# BOTTOM_BRD_v_1_0_3.net
KiCad netlist of a schematic drawn in EAGLE
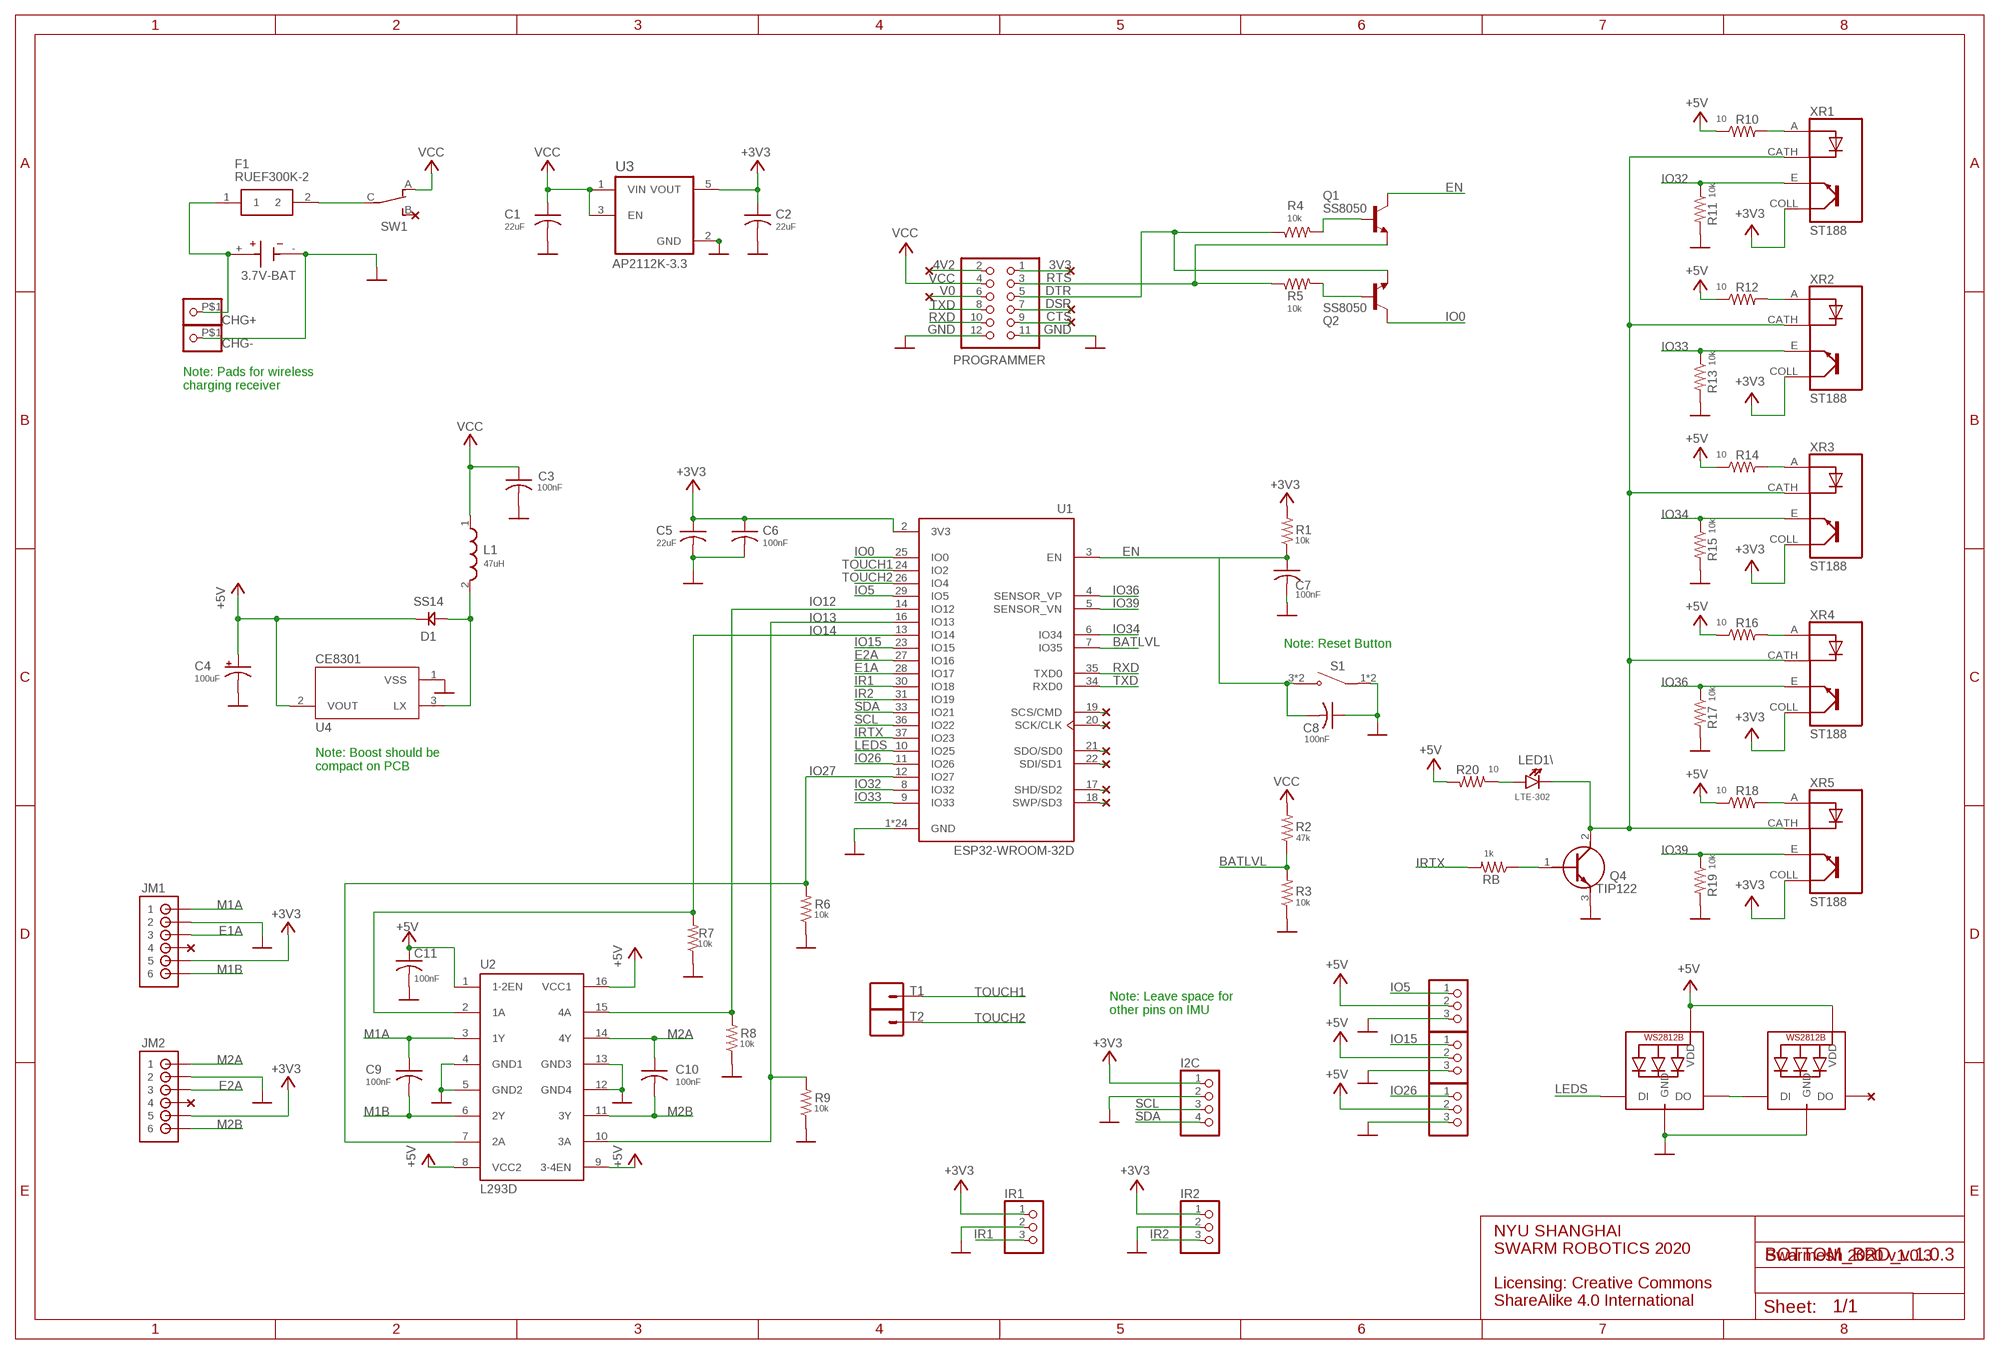
[diagram p0: schematic, sheet 1]

(export (version "E")
  (design (tool "Eeschema 10.0.6"))
  (components
    (comp (ref "BT")
      (value "3.7V-BAT")
      (footprint "eagle-import:BAT_6S-AA")
      (fields (field (name "MF") "MPD") (field (name "MP") "6S-AA"))
      (libsource (lib "eagle-import") (part "6S-AA"))
    )
    (comp (ref "C1")
      (value "22uF")
      (footprint "eagle-import:C0805")
      (libsource (lib "eagle-import") (part "C-USC0805"))
    )
    (comp (ref "C2")
      (value "22uF")
      (footprint "eagle-import:C0805")
      (libsource (lib "eagle-import") (part "C-USC0805"))
    )
    (comp (ref "C3")
      (value "100nF")
      (footprint "eagle-import:C0805")
      (libsource (lib "eagle-import") (part "C-USC0805"))
    )
    (comp (ref "C4")
      (value "100uF")
      (footprint "eagle-import:153CLV-0605")
      (libsource (lib "eagle-import") (part "CPOL-US153CLV-0605"))
    )
    (comp (ref "C5")
      (value "22uF")
      (footprint "eagle-import:C0805")
      (libsource (lib "eagle-import") (part "C-USC0805"))
    )
    (comp (ref "C6")
      (value "100nF")
      (footprint "eagle-import:C0805")
      (libsource (lib "eagle-import") (part "C-USC0805"))
    )
    (comp (ref "C7")
      (value "100nF")
      (footprint "eagle-import:C0805")
      (libsource (lib "eagle-import") (part "C-USC0805"))
    )
    (comp (ref "C8")
      (value "100nF")
      (footprint "eagle-import:C0805")
      (libsource (lib "eagle-import") (part "C-USC0805"))
    )
    (comp (ref "C9")
      (value "100nF")
      (footprint "eagle-import:C0805")
      (libsource (lib "eagle-import") (part "C-USC0805"))
    )
    (comp (ref "C10")
      (value "100nF")
      (footprint "eagle-import:C0805")
      (libsource (lib "eagle-import") (part "C-USC0805"))
    )
    (comp (ref "C11")
      (value "100nF")
      (footprint "eagle-import:C0805")
      (libsource (lib "eagle-import") (part "C-USC0805"))
    )
    (comp (ref "CHARGING")
      (value "WS2812B5050")
      (footprint "eagle-import:WS2812B")
      (libsource (lib "eagle-import") (part "WS2812B5050"))
    )
    (comp (ref "CHG+")
      (value "PINHD-1X1-BIGPOGO")
      (footprint "eagle-import:1X1-BIGPOGO")
      (libsource (lib "eagle-import") (part "PINHD-1X1-BIGPOGO"))
    )
    (comp (ref "CHG-")
      (value "PINHD-1X1-BIGPOGO")
      (footprint "eagle-import:1X1-BIGPOGO")
      (libsource (lib "eagle-import") (part "PINHD-1X1-BIGPOGO"))
    )
    (comp (ref "D1")
      (value "SS14")
      (footprint "eagle-import:DO214")
      (fields (field (name "MF") "ON Semiconductor"))
      (libsource (lib "eagle-import") (part "SS14"))
    )
    (comp (ref "F1")
      (value "RUEF300K-2")
      (footprint "eagle-import:RUEF300K2")
      (libsource (lib "eagle-import") (part "RUEF300K-2"))
    )
    (comp (ref "GPIO5")
      (value "PINHD-1X3")
      (footprint "eagle-import:1X03")
      (libsource (lib "eagle-import") (part "PINHD-1X3"))
    )
    (comp (ref "GPIO15")
      (value "PINHD-1X3")
      (footprint "eagle-import:1X03")
      (libsource (lib "eagle-import") (part "PINHD-1X3"))
    )
    (comp (ref "GPIO26")
      (value "PINHD-1X3")
      (footprint "eagle-import:1X03")
      (libsource (lib "eagle-import") (part "PINHD-1X3"))
    )
    (comp (ref "I2C")
      (value "PINHD-1X4")
      (footprint "eagle-import:1X04")
      (libsource (lib "eagle-import") (part "PINHD-1X4"))
    )
    (comp (ref "IR1")
      (value "PINHD-1X3")
      (footprint "eagle-import:1X03")
      (libsource (lib "eagle-import") (part "PINHD-1X3"))
    )
    (comp (ref "IR2")
      (value "PINHD-1X3")
      (footprint "eagle-import:1X03")
      (libsource (lib "eagle-import") (part "PINHD-1X3"))
    )
    (comp (ref "JM1")
      (value "B6B-ZR")
      (footprint "eagle-import:B6B-ZR")
      (fields (field (name "MF") "JST"))
      (libsource (lib "eagle-import") (part "B6B-ZR"))
    )
    (comp (ref "JM2")
      (value "B6B-ZR")
      (footprint "eagle-import:B6B-ZR")
      (fields (field (name "MF") "JST"))
      (libsource (lib "eagle-import") (part "B6B-ZR"))
    )
    (comp (ref "L1")
      (value "47uH")
      (footprint "eagle-import:INDP5858X480N")
      (fields (field (name "MF") "Bourns") (field (name "MP") "SDR0604-100KL"))
      (libsource (lib "eagle-import") (part "SDR0604-100KL"))
    )
    (comp (ref "LED1\\")
      (value "LTE-302")
      (footprint "eagle-import:LTE-302")
      (fields (field (name "DIGI-KEY_PART_NUMBER") "160-1930-ND") (field (name "MF") "Lite-On Inc."))
      (libsource (lib "eagle-import") (part "LTE-302"))
    )
    (comp (ref "PROGRAMMER")
      (value "PINHD-2X6")
      (footprint "eagle-import:2X06")
      (libsource (lib "eagle-import") (part "PINHD-2X6"))
    )
    (comp (ref "Q1")
      (value "SS8050")
      (footprint "eagle-import:SOT23")
      (libsource (lib "eagle-import") (part "BC850"))
    )
    (comp (ref "Q2")
      (value "SS8050")
      (footprint "eagle-import:SOT23")
      (libsource (lib "eagle-import") (part "BC850"))
    )
    (comp (ref "Q4")
      (value "TIP122")
      (footprint "eagle-import:TO270P460X1020X2008-3P")
      (fields (field (name "MOUSER_PART_NUMBER") "511-TIP122"))
      (libsource (lib "eagle-import") (part "TIP122"))
    )
    (comp (ref "R1")
      (value "10k")
      (footprint "eagle-import:M0805")
      (libsource (lib "eagle-import") (part "R-US_M0805"))
    )
    (comp (ref "R2")
      (value "47k")
      (footprint "eagle-import:M0805")
      (libsource (lib "eagle-import") (part "R-US_M0805"))
    )
    (comp (ref "R3")
      (value "10k")
      (footprint "eagle-import:M0805")
      (libsource (lib "eagle-import") (part "R-US_M0805"))
    )
    (comp (ref "R4")
      (value "10k")
      (footprint "eagle-import:M0805")
      (libsource (lib "eagle-import") (part "R-US_M0805"))
    )
    (comp (ref "R5")
      (value "10k")
      (footprint "eagle-import:M0805")
      (libsource (lib "eagle-import") (part "R-US_M0805"))
    )
    (comp (ref "R6")
      (value "10k")
      (footprint "eagle-import:M0805")
      (libsource (lib "eagle-import") (part "R-US_M0805"))
    )
    (comp (ref "R7")
      (value "10k")
      (footprint "eagle-import:M0805")
      (libsource (lib "eagle-import") (part "R-US_M0805"))
    )
    (comp (ref "R8")
      (value "10k")
      (footprint "eagle-import:M0805")
      (libsource (lib "eagle-import") (part "R-US_M0805"))
    )
    (comp (ref "R9")
      (value "10k")
      (footprint "eagle-import:M0805")
      (libsource (lib "eagle-import") (part "R-US_M0805"))
    )
    (comp (ref "R10")
      (value "10")
      (footprint "eagle-import:M0805")
      (libsource (lib "eagle-import") (part "R-US_M0805"))
    )
    (comp (ref "R11")
      (value "10k")
      (footprint "eagle-import:M0805")
      (libsource (lib "eagle-import") (part "R-US_M0805"))
    )
    (comp (ref "R12")
      (value "10")
      (footprint "eagle-import:M0805")
      (libsource (lib "eagle-import") (part "R-US_M0805"))
    )
    (comp (ref "R13")
      (value "10k")
      (footprint "eagle-import:M0805")
      (libsource (lib "eagle-import") (part "R-US_M0805"))
    )
    (comp (ref "R14")
      (value "10")
      (footprint "eagle-import:M0805")
      (libsource (lib "eagle-import") (part "R-US_M0805"))
    )
    (comp (ref "R15")
      (value "10k")
      (footprint "eagle-import:M0805")
      (libsource (lib "eagle-import") (part "R-US_M0805"))
    )
    (comp (ref "R16")
      (value "10")
      (footprint "eagle-import:M0805")
      (libsource (lib "eagle-import") (part "R-US_M0805"))
    )
    (comp (ref "R17")
      (value "10k")
      (footprint "eagle-import:M0805")
      (libsource (lib "eagle-import") (part "R-US_M0805"))
    )
    (comp (ref "R18")
      (value "10")
      (footprint "eagle-import:M0805")
      (libsource (lib "eagle-import") (part "R-US_M0805"))
    )
    (comp (ref "R19")
      (value "10k")
      (footprint "eagle-import:M0805")
      (libsource (lib "eagle-import") (part "R-US_M0805"))
    )
    (comp (ref "R20")
      (value "10")
      (footprint "eagle-import:M0805")
      (libsource (lib "eagle-import") (part "R-US_M0805"))
    )
    (comp (ref "RB")
      (value "1k")
      (footprint "eagle-import:M0805")
      (libsource (lib "eagle-import") (part "R-US_M0805"))
    )
    (comp (ref "S1")
      (value "2-1437565-9")
      (footprint "eagle-import:SW_2-1437565-9")
      (fields (field (name "MF") "TE Connectivity"))
      (libsource (lib "eagle-import") (part "2-1437565-9"))
    )
    (comp (ref "STATE")
      (value "WS2812B5050")
      (footprint "eagle-import:WS2812B")
      (libsource (lib "eagle-import") (part "WS2812B5050"))
    )
    (comp (ref "SW1")
      (value "CS12ANW03")
      (footprint "eagle-import:CS12ANW03")
      (fields (field (name "MF") "NKK Switches"))
      (libsource (lib "eagle-import") (part "CS12ANW03"))
    )
    (comp (ref "T1")
      (value "CONN_01SPRING-CONN")
      (footprint "eagle-import:SPRING-CONNECTOR")
      (libsource (lib "eagle-import") (part "CONN_01SPRING-CONN"))
    )
    (comp (ref "T2")
      (value "CONN_01SPRING-CONN")
      (footprint "eagle-import:SPRING-CONNECTOR")
      (libsource (lib "eagle-import") (part "CONN_01SPRING-CONN"))
    )
    (comp (ref "U1")
      (value "ESP32-WROOM-32D")
      (footprint "eagle-import:MODULE_ESP32-WROOM-32D")
      (fields (field (name "MF") "Espressif Systems"))
      (libsource (lib "eagle-import") (part "ESP32-WROOM-32D"))
    )
    (comp (ref "U2")
      (value "L293D")
      (footprint "eagle-import:DIL16")
      (libsource (lib "eagle-import") (part "L293D"))
    )
    (comp (ref "U3")
      (value "AP2112K-3.3")
      (footprint "eagle-import:SOT95P285X140-5N")
      (fields (field (name "MF") "Diodes Inc.") (field (name "MP") "AP2112K-3.3TRG1"))
      (libsource (lib "eagle-import") (part "AP2112K-3.3TRG1"))
    )
    (comp (ref "U4")
      (value "CE8301")
      (footprint "eagle-import:REG_MCP1702T-3302E_MB")
      (fields (field (name "MF") "Microchip") (field (name "MP") "MCP1702T-3302E/MB"))
      (libsource (lib "eagle-import") (part "MCP1702T-3302E/MB"))
    )
    (comp (ref "XR1")
      (value "ST188")
      (footprint "eagle-import:XDCR_TCRT1000")
      (fields (field (name "MF") "Vishay") (field (name "MP") "TCRT1000"))
      (libsource (lib "eagle-import") (part "TCRT1000"))
    )
    (comp (ref "XR2")
      (value "ST188")
      (footprint "eagle-import:XDCR_TCRT1000")
      (fields (field (name "MF") "Vishay") (field (name "MP") "TCRT1000"))
      (libsource (lib "eagle-import") (part "TCRT1000"))
    )
    (comp (ref "XR3")
      (value "ST188")
      (footprint "eagle-import:XDCR_TCRT1000")
      (fields (field (name "MF") "Vishay") (field (name "MP") "TCRT1000"))
      (libsource (lib "eagle-import") (part "TCRT1000"))
    )
    (comp (ref "XR4")
      (value "ST188")
      (footprint "eagle-import:XDCR_TCRT1000")
      (fields (field (name "MF") "Vishay") (field (name "MP") "TCRT1000"))
      (libsource (lib "eagle-import") (part "TCRT1000"))
    )
    (comp (ref "XR5")
      (value "ST188")
      (footprint "eagle-import:XDCR_TCRT1000")
      (fields (field (name "MF") "Vishay") (field (name "MP") "TCRT1000"))
      (libsource (lib "eagle-import") (part "TCRT1000"))
    )
  )
  (nets
    (net (code "1") (name "+3V3") (class "Default")
      (node (ref "C2") (pin "1") (pinfunction "1_1") (pintype "passive"))
      (node (ref "C5") (pin "1") (pinfunction "1_1") (pintype "passive"))
      (node (ref "C6") (pin "1") (pinfunction "1_1") (pintype "passive"))
      (node (ref "I2C") (pin "1") (pinfunction "1_1") (pintype "passive"))
      (node (ref "IR1") (pin "1") (pinfunction "1_1") (pintype "passive"))
      (node (ref "IR2") (pin "1") (pinfunction "1_1") (pintype "passive"))
      (node (ref "JM1") (pin "5") (pinfunction "5_5") (pintype "bidirectional"))
      (node (ref "JM2") (pin "5") (pinfunction "5_5") (pintype "bidirectional"))
      (node (ref "R1") (pin "2") (pinfunction "2_2") (pintype "passive"))
      (node (ref "U1") (pin "2") (pinfunction "3V3_2") (pintype "power_in"))
      (node (ref "U3") (pin "5") (pinfunction "VOUT_5") (pintype "power_in"))
      (node (ref "XR1") (pin "COLL") (pinfunction "CO_COLL") (pintype "passive"))
      (node (ref "XR2") (pin "COLL") (pinfunction "CO_COLL") (pintype "passive"))
      (node (ref "XR3") (pin "COLL") (pinfunction "CO_COLL") (pintype "passive"))
      (node (ref "XR4") (pin "COLL") (pinfunction "CO_COLL") (pintype "passive"))
      (node (ref "XR5") (pin "COLL") (pinfunction "CO_COLL") (pintype "passive"))
    )
    (net (code "2") (name "+5V") (class "Default")
      (node (ref "C11") (pin "1") (pinfunction "1_1") (pintype "passive"))
      (node (ref "C4") (pin "+") (pinfunction "+_+") (pintype "passive"))
      (node (ref "CHARGING") (pin "1-VDD") (pinfunction "VDD_1-VDD") (pintype "power_in"))
      (node (ref "D1") (pin "CATHODE") (pinfunction "KATHODE_CATHODE") (pintype "bidirectional"))
      (node (ref "GPIO15") (pin "2") (pinfunction "2_2") (pintype "passive"))
      (node (ref "GPIO26") (pin "2") (pinfunction "2_2") (pintype "passive"))
      (node (ref "GPIO5") (pin "2") (pinfunction "2_2") (pintype "passive"))
      (node (ref "R10") (pin "1") (pinfunction "1_1") (pintype "passive"))
      (node (ref "R12") (pin "1") (pinfunction "1_1") (pintype "passive"))
      (node (ref "R14") (pin "1") (pinfunction "1_1") (pintype "passive"))
      (node (ref "R16") (pin "1") (pinfunction "1_1") (pintype "passive"))
      (node (ref "R18") (pin "1") (pinfunction "1_1") (pintype "passive"))
      (node (ref "R20") (pin "2") (pinfunction "2_2") (pintype "passive"))
      (node (ref "STATE") (pin "1-VDD") (pinfunction "VDD_1-VDD") (pintype "power_in"))
      (node (ref "U2") (pin "1") (pinfunction "1-2EN_1") (pintype "input"))
      (node (ref "U2") (pin "16") (pinfunction "VCC1_16") (pintype "power_in"))
      (node (ref "U2") (pin "8") (pinfunction "VCC2_8") (pintype "power_in"))
      (node (ref "U2") (pin "9") (pinfunction "3-4EN_9") (pintype "input"))
      (node (ref "U4") (pin "2") (pinfunction "VOUT_2") (pintype "input"))
    )
    (net (code "3") (name "/3V3") (class "Default")
      (node (ref "PROGRAMMER") (pin "1") (pinfunction "1_1") (pintype "passive"))
    )
    (net (code "4") (name "/4V2") (class "Default")
      (node (ref "PROGRAMMER") (pin "2") (pinfunction "2_2") (pintype "passive"))
    )
    (net (code "5") (name "/BATLVL") (class "Default")
      (node (ref "R2") (pin "1") (pinfunction "1_1") (pintype "passive"))
      (node (ref "R3") (pin "2") (pinfunction "2_2") (pintype "passive"))
      (node (ref "U1") (pin "7") (pinfunction "IO35_7") (pintype "input"))
    )
    (net (code "6") (name "/CTS") (class "Default")
      (node (ref "PROGRAMMER") (pin "9") (pinfunction "9_9") (pintype "passive"))
    )
    (net (code "7") (name "/DSR") (class "Default")
      (node (ref "PROGRAMMER") (pin "7") (pinfunction "7_7") (pintype "passive"))
    )
    (net (code "8") (name "/DTR") (class "Default")
      (node (ref "PROGRAMMER") (pin "5") (pinfunction "5_5") (pintype "passive"))
      (node (ref "Q2") (pin "2") (pinfunction "E_2") (pintype "passive"))
      (node (ref "R4") (pin "1") (pinfunction "1_1") (pintype "passive"))
    )
    (net (code "9") (name "/E1A") (class "Default")
      (node (ref "JM1") (pin "3") (pinfunction "3_3") (pintype "bidirectional"))
      (node (ref "U1") (pin "28") (pinfunction "IO17_28") (pintype "bidirectional"))
    )
    (net (code "10") (name "/E2A") (class "Default")
      (node (ref "JM2") (pin "3") (pinfunction "3_3") (pintype "bidirectional"))
      (node (ref "U1") (pin "27") (pinfunction "IO16_27") (pintype "bidirectional"))
    )
    (net (code "11") (name "/EN") (class "Default")
      (node (ref "C7") (pin "1") (pinfunction "1_1") (pintype "passive"))
      (node (ref "C8") (pin "2") (pinfunction "2_2") (pintype "passive"))
      (node (ref "Q1") (pin "3") (pinfunction "C_3") (pintype "passive"))
      (node (ref "R1") (pin "1") (pinfunction "1_1") (pintype "passive"))
      (node (ref "S1") (pin "3") (pinfunction "NO_3") (pintype "passive"))
      (node (ref "S1") (pin "4") (pinfunction "NO_4") (pintype "passive"))
      (node (ref "U1") (pin "3") (pinfunction "EN_3") (pintype "input"))
    )
    (net (code "12") (name "/IO0") (class "Default")
      (node (ref "Q2") (pin "3") (pinfunction "C_3") (pintype "passive"))
      (node (ref "U1") (pin "25") (pinfunction "IO0_25") (pintype "bidirectional"))
    )
    (net (code "13") (name "/IO5") (class "Default")
      (node (ref "GPIO5") (pin "1") (pinfunction "1_1") (pintype "passive"))
      (node (ref "U1") (pin "29") (pinfunction "IO5_29") (pintype "bidirectional"))
    )
    (net (code "14") (name "/IO12") (class "Default")
      (node (ref "R8") (pin "2") (pinfunction "2_2") (pintype "passive"))
      (node (ref "U1") (pin "14") (pinfunction "IO12_14") (pintype "bidirectional"))
      (node (ref "U2") (pin "15") (pinfunction "4A_15") (pintype "input"))
    )
    (net (code "15") (name "/IO13") (class "Default")
      (node (ref "R9") (pin "2") (pinfunction "2_2") (pintype "passive"))
      (node (ref "U1") (pin "16") (pinfunction "IO13_16") (pintype "bidirectional"))
      (node (ref "U2") (pin "10") (pinfunction "3A_10") (pintype "input"))
    )
    (net (code "16") (name "/IO14") (class "Default")
      (node (ref "R7") (pin "2") (pinfunction "2_2") (pintype "passive"))
      (node (ref "U1") (pin "13") (pinfunction "IO14_13") (pintype "bidirectional"))
      (node (ref "U2") (pin "2") (pinfunction "1A_2") (pintype "input"))
    )
    (net (code "17") (name "/IO15") (class "Default")
      (node (ref "GPIO15") (pin "1") (pinfunction "1_1") (pintype "passive"))
      (node (ref "U1") (pin "23") (pinfunction "IO15_23") (pintype "bidirectional"))
    )
    (net (code "18") (name "/IO26") (class "Default")
      (node (ref "GPIO26") (pin "1") (pinfunction "1_1") (pintype "passive"))
      (node (ref "U1") (pin "11") (pinfunction "IO26_11") (pintype "bidirectional"))
    )
    (net (code "19") (name "/IO27") (class "Default")
      (node (ref "R6") (pin "2") (pinfunction "2_2") (pintype "passive"))
      (node (ref "U1") (pin "12") (pinfunction "IO27_12") (pintype "bidirectional"))
      (node (ref "U2") (pin "7") (pinfunction "2A_7") (pintype "input"))
    )
    (net (code "20") (name "/IO32") (class "Default")
      (node (ref "R11") (pin "1") (pinfunction "1_1") (pintype "passive"))
      (node (ref "U1") (pin "8") (pinfunction "IO32_8") (pintype "bidirectional"))
      (node (ref "XR1") (pin "E") (pinfunction "E_E") (pintype "passive"))
    )
    (net (code "21") (name "/IO33") (class "Default")
      (node (ref "R13") (pin "1") (pinfunction "1_1") (pintype "passive"))
      (node (ref "U1") (pin "9") (pinfunction "IO33_9") (pintype "bidirectional"))
      (node (ref "XR2") (pin "E") (pinfunction "E_E") (pintype "passive"))
    )
    (net (code "22") (name "/IO34") (class "Default")
      (node (ref "R15") (pin "1") (pinfunction "1_1") (pintype "passive"))
      (node (ref "U1") (pin "6") (pinfunction "IO34_6") (pintype "input"))
      (node (ref "XR3") (pin "E") (pinfunction "E_E") (pintype "passive"))
    )
    (net (code "23") (name "/IO36") (class "Default")
      (node (ref "R17") (pin "1") (pinfunction "1_1") (pintype "passive"))
      (node (ref "U1") (pin "4") (pinfunction "SENSOR_VP_4") (pintype "input"))
      (node (ref "XR4") (pin "E") (pinfunction "E_E") (pintype "passive"))
    )
    (net (code "24") (name "/IO39") (class "Default")
      (node (ref "R19") (pin "1") (pinfunction "1_1") (pintype "passive"))
      (node (ref "U1") (pin "5") (pinfunction "SENSOR_VN_5") (pintype "input"))
      (node (ref "XR5") (pin "E") (pinfunction "E_E") (pintype "passive"))
    )
    (net (code "25") (name "/IR1") (class "Default")
      (node (ref "IR1") (pin "3") (pinfunction "3_3") (pintype "passive"))
      (node (ref "U1") (pin "30") (pinfunction "IO18_30") (pintype "bidirectional"))
    )
    (net (code "26") (name "/IR2") (class "Default")
      (node (ref "IR2") (pin "3") (pinfunction "3_3") (pintype "passive"))
      (node (ref "U1") (pin "31") (pinfunction "IO19_31") (pintype "bidirectional"))
    )
    (net (code "27") (name "/IRTX") (class "Default")
      (node (ref "RB") (pin "2") (pinfunction "2_2") (pintype "passive"))
      (node (ref "U1") (pin "37") (pinfunction "IO23_37") (pintype "bidirectional"))
    )
    (net (code "28") (name "/LEDS") (class "Default")
      (node (ref "CHARGING") (pin "4-DIN") (pinfunction "DI_4-DIN") (pintype "input"))
      (node (ref "U1") (pin "10") (pinfunction "IO25_10") (pintype "bidirectional"))
    )
    (net (code "29") (name "/M1A") (class "Default")
      (node (ref "C9") (pin "1") (pinfunction "1_1") (pintype "passive"))
      (node (ref "JM1") (pin "1") (pinfunction "1_1") (pintype "bidirectional"))
      (node (ref "U2") (pin "3") (pinfunction "1Y_3") (pintype "output"))
    )
    (net (code "30") (name "/M1B") (class "Default")
      (node (ref "C9") (pin "2") (pinfunction "2_2") (pintype "passive"))
      (node (ref "JM1") (pin "6") (pinfunction "6_6") (pintype "bidirectional"))
      (node (ref "U2") (pin "6") (pinfunction "2Y_6") (pintype "output"))
    )
    (net (code "31") (name "/M2A") (class "Default")
      (node (ref "C10") (pin "1") (pinfunction "1_1") (pintype "passive"))
      (node (ref "JM2") (pin "1") (pinfunction "1_1") (pintype "bidirectional"))
      (node (ref "U2") (pin "14") (pinfunction "4Y_14") (pintype "output"))
    )
    (net (code "32") (name "/M2B") (class "Default")
      (node (ref "C10") (pin "2") (pinfunction "2_2") (pintype "passive"))
      (node (ref "JM2") (pin "6") (pinfunction "6_6") (pintype "bidirectional"))
      (node (ref "U2") (pin "11") (pinfunction "3Y_11") (pintype "output"))
    )
    (net (code "33") (name "/RTS") (class "Default")
      (node (ref "PROGRAMMER") (pin "3") (pinfunction "3_3") (pintype "passive"))
      (node (ref "Q1") (pin "2") (pinfunction "E_2") (pintype "passive"))
      (node (ref "R5") (pin "1") (pinfunction "1_1") (pintype "passive"))
    )
    (net (code "34") (name "/RXD") (class "Default")
      (node (ref "PROGRAMMER") (pin "10") (pinfunction "10_10") (pintype "passive"))
      (node (ref "U1") (pin "35") (pinfunction "TXD0_35") (pintype "bidirectional"))
    )
    (net (code "35") (name "/SCL") (class "Default")
      (node (ref "I2C") (pin "3") (pinfunction "3_3") (pintype "passive"))
      (node (ref "U1") (pin "36") (pinfunction "IO22_36") (pintype "bidirectional"))
    )
    (net (code "36") (name "/SDA") (class "Default")
      (node (ref "I2C") (pin "4") (pinfunction "4_4") (pintype "passive"))
      (node (ref "U1") (pin "33") (pinfunction "IO21_33") (pintype "bidirectional"))
    )
    (net (code "37") (name "/TOUCH1") (class "Default")
      (node (ref "T1") (pin "P$2") (pinfunction "1_P$2") (pintype "passive"))
      (node (ref "U1") (pin "24") (pinfunction "IO2_24") (pintype "bidirectional"))
    )
    (net (code "38") (name "/TOUCH2") (class "Default")
      (node (ref "T2") (pin "P$2") (pinfunction "1_P$2") (pintype "passive"))
      (node (ref "U1") (pin "26") (pinfunction "IO4_26") (pintype "bidirectional"))
    )
    (net (code "39") (name "/TXD") (class "Default")
      (node (ref "PROGRAMMER") (pin "8") (pinfunction "8_8") (pintype "passive"))
      (node (ref "U1") (pin "34") (pinfunction "RXD0_34") (pintype "bidirectional"))
    )
    (net (code "40") (name "/V0") (class "Default")
      (node (ref "PROGRAMMER") (pin "6") (pinfunction "6_6") (pintype "passive"))
    )
    (net (code "41") (name "GND") (class "Default")
      (node (ref "BT") (pin "-") (pinfunction "-_-") (pintype "passive"))
      (node (ref "C1") (pin "2") (pinfunction "2_2") (pintype "passive"))
      (node (ref "C11") (pin "2") (pinfunction "2_2") (pintype "passive"))
      (node (ref "C2") (pin "2") (pinfunction "2_2") (pintype "passive"))
      (node (ref "C3") (pin "2") (pinfunction "2_2") (pintype "passive"))
      (node (ref "C4") (pin "-") (pinfunction "-_-") (pintype "passive"))
      (node (ref "C5") (pin "2") (pinfunction "2_2") (pintype "passive"))
      (node (ref "C6") (pin "2") (pinfunction "2_2") (pintype "passive"))
      (node (ref "C7") (pin "2") (pinfunction "2_2") (pintype "passive"))
      (node (ref "C8") (pin "1") (pinfunction "1_1") (pintype "passive"))
      (node (ref "CHARGING") (pin "3-GND") (pinfunction "GND_3-GND") (pintype "power_in"))
      (node (ref "CHG-") (pin "P$1") (pinfunction "1_P$1") (pintype "passive"))
      (node (ref "GPIO15") (pin "3") (pinfunction "3_3") (pintype "passive"))
      (node (ref "GPIO26") (pin "3") (pinfunction "3_3") (pintype "passive"))
      (node (ref "GPIO5") (pin "3") (pinfunction "3_3") (pintype "passive"))
      (node (ref "I2C") (pin "2") (pinfunction "2_2") (pintype "passive"))
      (node (ref "IR1") (pin "2") (pinfunction "2_2") (pintype "passive"))
      (node (ref "IR2") (pin "2") (pinfunction "2_2") (pintype "passive"))
      (node (ref "JM1") (pin "2") (pinfunction "2_2") (pintype "bidirectional"))
      (node (ref "JM2") (pin "2") (pinfunction "2_2") (pintype "bidirectional"))
      (node (ref "PROGRAMMER") (pin "11") (pinfunction "11_11") (pintype "passive"))
      (node (ref "PROGRAMMER") (pin "12") (pinfunction "12_12") (pintype "passive"))
      (node (ref "Q4") (pin "3") (pinfunction "E_3") (pintype "bidirectional"))
      (node (ref "R11") (pin "2") (pinfunction "2_2") (pintype "passive"))
      (node (ref "R13") (pin "2") (pinfunction "2_2") (pintype "passive"))
      (node (ref "R15") (pin "2") (pinfunction "2_2") (pintype "passive"))
      (node (ref "R17") (pin "2") (pinfunction "2_2") (pintype "passive"))
      (node (ref "R19") (pin "2") (pinfunction "2_2") (pintype "passive"))
      (node (ref "R3") (pin "1") (pinfunction "1_1") (pintype "passive"))
      (node (ref "R6") (pin "1") (pinfunction "1_1") (pintype "passive"))
      (node (ref "R7") (pin "1") (pinfunction "1_1") (pintype "passive"))
      (node (ref "R8") (pin "1") (pinfunction "1_1") (pintype "passive"))
      (node (ref "R9") (pin "1") (pinfunction "1_1") (pintype "passive"))
      (node (ref "S1") (pin "1") (pinfunction "COM_1") (pintype "passive"))
      (node (ref "S1") (pin "2") (pinfunction "COM_2") (pintype "passive"))
      (node (ref "STATE") (pin "3-GND") (pinfunction "GND_3-GND") (pintype "power_in"))
      (node (ref "U1") (pin "1") (pinfunction "GND_1") (pintype "power_in"))
      (node (ref "U1") (pin "15") (pinfunction "GND_15") (pintype "power_in"))
      (node (ref "U1") (pin "38") (pinfunction "GND_38") (pintype "power_in"))
      (node (ref "U1") (pin "39_1") (pinfunction "GND_39_1") (pintype "power_in"))
      (node (ref "U1") (pin "39_10") (pinfunction "GND_39_10") (pintype "power_in"))
      (node (ref "U1") (pin "39_11") (pinfunction "GND_39_11") (pintype "power_in"))
      (node (ref "U1") (pin "39_12") (pinfunction "GND_39_12") (pintype "power_in"))
      (node (ref "U1") (pin "39_13") (pinfunction "GND_39_13") (pintype "power_in"))
      (node (ref "U1") (pin "39_14") (pinfunction "GND_39_14") (pintype "power_in"))
      (node (ref "U1") (pin "39_15") (pinfunction "GND_39_15") (pintype "power_in"))
      (node (ref "U1") (pin "39_16") (pinfunction "GND_39_16") (pintype "power_in"))
      (node (ref "U1") (pin "39_17") (pinfunction "GND_39_17") (pintype "power_in"))
      (node (ref "U1") (pin "39_18") (pinfunction "GND_39_18") (pintype "power_in"))
      (node (ref "U1") (pin "39_19") (pinfunction "GND_39_19") (pintype "power_in"))
      (node (ref "U1") (pin "39_2") (pinfunction "GND_39_2") (pintype "power_in"))
      (node (ref "U1") (pin "39_20") (pinfunction "GND_39_20") (pintype "power_in"))
      (node (ref "U1") (pin "39_21") (pinfunction "GND_39_21") (pintype "power_in"))
      (node (ref "U1") (pin "39_3") (pinfunction "GND_39_3") (pintype "power_in"))
      (node (ref "U1") (pin "39_4") (pinfunction "GND_39_4") (pintype "power_in"))
      (node (ref "U1") (pin "39_5") (pinfunction "GND_39_5") (pintype "power_in"))
      (node (ref "U1") (pin "39_6") (pinfunction "GND_39_6") (pintype "power_in"))
      (node (ref "U1") (pin "39_7") (pinfunction "GND_39_7") (pintype "power_in"))
      (node (ref "U1") (pin "39_8") (pinfunction "GND_39_8") (pintype "power_in"))
      (node (ref "U1") (pin "39_9") (pinfunction "GND_39_9") (pintype "power_in"))
      (node (ref "U2") (pin "12") (pinfunction "GND4_12") (pintype "power_in"))
      (node (ref "U2") (pin "13") (pinfunction "GND3_13") (pintype "power_in"))
      (node (ref "U2") (pin "4") (pinfunction "GND1_4") (pintype "power_in"))
      (node (ref "U2") (pin "5") (pinfunction "GND2_5") (pintype "power_in"))
      (node (ref "U3") (pin "2") (pinfunction "GND_2") (pintype "power_in"))
      (node (ref "U4") (pin "1") (pinfunction "VSS_1") (pintype "power_in"))
    )
    (net (code "42") (name "Net-(CHARGING-DO)") (class "Default")
      (node (ref "CHARGING") (pin "2-DOUT") (pinfunction "DO_2-DOUT") (pintype "output"))
      (node (ref "STATE") (pin "4-DIN") (pinfunction "DI_4-DIN") (pintype "input"))
    )
    (net (code "43") (name "Net-(CHG+-1)") (class "Default")
      (node (ref "BT") (pin "+") (pinfunction "+_+") (pintype "passive"))
      (node (ref "CHG+") (pin "P$1") (pinfunction "1_P$1") (pintype "passive"))
      (node (ref "F1") (pin "1") (pinfunction "1_1") (pintype "bidirectional"))
    )
    (net (code "44") (name "Net-(F1-Pad2)") (class "Default")
      (node (ref "F1") (pin "2") (pinfunction "2_2") (pintype "bidirectional"))
      (node (ref "SW1") (pin "C") (pinfunction "C_C") (pintype "passive"))
    )
    (net (code "45") (name "Net-(LED1\\-PadA)") (class "Default")
      (node (ref "LED1\\") (pin "A") (pinfunction "A_A") (pintype "bidirectional"))
      (node (ref "R20") (pin "1") (pinfunction "1_1") (pintype "passive"))
    )
    (net (code "46") (name "Net-(Q1-B)") (class "Default")
      (node (ref "Q1") (pin "1") (pinfunction "B_1") (pintype "passive"))
      (node (ref "R4") (pin "2") (pinfunction "2_2") (pintype "passive"))
    )
    (net (code "47") (name "Net-(Q2-B)") (class "Default")
      (node (ref "Q2") (pin "1") (pinfunction "B_1") (pintype "passive"))
      (node (ref "R5") (pin "2") (pinfunction "2_2") (pintype "passive"))
    )
    (net (code "48") (name "Net-(Q4-B)") (class "Default")
      (node (ref "Q4") (pin "1") (pinfunction "B_1") (pintype "bidirectional"))
      (node (ref "RB") (pin "1") (pinfunction "1_1") (pintype "passive"))
    )
    (net (code "49") (name "Net-(Q4-C)") (class "Default")
      (node (ref "LED1\\") (pin "C") (pinfunction "C_C") (pintype "bidirectional"))
      (node (ref "Q4") (pin "2") (pinfunction "C_2") (pintype "bidirectional"))
      (node (ref "XR1") (pin "CATH") (pinfunction "C_CATH") (pintype "passive"))
      (node (ref "XR2") (pin "CATH") (pinfunction "C_CATH") (pintype "passive"))
      (node (ref "XR3") (pin "CATH") (pinfunction "C_CATH") (pintype "passive"))
      (node (ref "XR4") (pin "CATH") (pinfunction "C_CATH") (pintype "passive"))
      (node (ref "XR5") (pin "CATH") (pinfunction "C_CATH") (pintype "passive"))
    )
    (net (code "50") (name "Net-(R10-Pad2)") (class "Default")
      (node (ref "R10") (pin "2") (pinfunction "2_2") (pintype "passive"))
      (node (ref "XR1") (pin "A") (pinfunction "A_A") (pintype "passive"))
    )
    (net (code "51") (name "Net-(R12-Pad2)") (class "Default")
      (node (ref "R12") (pin "2") (pinfunction "2_2") (pintype "passive"))
      (node (ref "XR2") (pin "A") (pinfunction "A_A") (pintype "passive"))
    )
    (net (code "52") (name "Net-(R14-Pad2)") (class "Default")
      (node (ref "R14") (pin "2") (pinfunction "2_2") (pintype "passive"))
      (node (ref "XR3") (pin "A") (pinfunction "A_A") (pintype "passive"))
    )
    (net (code "53") (name "Net-(R16-Pad2)") (class "Default")
      (node (ref "R16") (pin "2") (pinfunction "2_2") (pintype "passive"))
      (node (ref "XR4") (pin "A") (pinfunction "A_A") (pintype "passive"))
    )
    (net (code "54") (name "Net-(R18-Pad2)") (class "Default")
      (node (ref "R18") (pin "2") (pinfunction "2_2") (pintype "passive"))
      (node (ref "XR5") (pin "A") (pinfunction "A_A") (pintype "passive"))
    )
    (net (code "55") (name "Net-(U4-LX)") (class "Default")
      (node (ref "D1") (pin "ANODE") (pinfunction "ANODE_ANODE") (pintype "bidirectional"))
      (node (ref "L1") (pin "2") (pinfunction "2_2") (pintype "passive"))
      (node (ref "U4") (pin "3") (pinfunction "LX_3") (pintype "output"))
    )
    (net (code "56") (name "VCC") (class "Default")
      (node (ref "C1") (pin "1") (pinfunction "1_1") (pintype "passive"))
      (node (ref "C3") (pin "1") (pinfunction "1_1") (pintype "passive"))
      (node (ref "L1") (pin "1") (pinfunction "1_1") (pintype "passive"))
      (node (ref "PROGRAMMER") (pin "4") (pinfunction "4_4") (pintype "passive"))
      (node (ref "R2") (pin "2") (pinfunction "2_2") (pintype "passive"))
      (node (ref "SW1") (pin "A") (pinfunction "A_A") (pintype "passive"))
      (node (ref "U3") (pin "1") (pinfunction "VIN_1") (pintype "power_in"))
      (node (ref "U3") (pin "3") (pinfunction "EN_3") (pintype "input"))
    )
    (net (code "57") (name "unconnected-(JM1-Pad4)") (class "Default")
      (node (ref "JM1") (pin "4") (pinfunction "4_4") (pintype "bidirectional"))
    )
    (net (code "58") (name "unconnected-(JM2-Pad4)") (class "Default")
      (node (ref "JM2") (pin "4") (pinfunction "4_4") (pintype "bidirectional"))
    )
    (net (code "59") (name "unconnected-(STATE-DO-Pad2-DOUT)") (class "Default")
      (node (ref "STATE") (pin "2-DOUT") (pinfunction "DO_2-DOUT") (pintype "output"))
    )
    (net (code "60") (name "unconnected-(SW1-PadB)") (class "Default")
      (node (ref "SW1") (pin "B") (pinfunction "B_B") (pintype "passive"))
    )
    (net (code "61") (name "unconnected-(U1-SCK{slash}CLK-Pad20)") (class "Default")
      (node (ref "U1") (pin "20") (pinfunction "SCK/CLK_20") (pintype "bidirectional"))
    )
    (net (code "62") (name "unconnected-(U1-SCS{slash}CMD-Pad19)") (class "Default")
      (node (ref "U1") (pin "19") (pinfunction "SCS/CMD_19") (pintype "bidirectional"))
    )
    (net (code "63") (name "unconnected-(U1-SDI{slash}SD1-Pad22)") (class "Default")
      (node (ref "U1") (pin "22") (pinfunction "SDI/SD1_22") (pintype "bidirectional"))
    )
    (net (code "64") (name "unconnected-(U1-SDO{slash}SD0-Pad21)") (class "Default")
      (node (ref "U1") (pin "21") (pinfunction "SDO/SD0_21") (pintype "bidirectional"))
    )
    (net (code "65") (name "unconnected-(U1-SHD{slash}SD2-Pad17)") (class "Default")
      (node (ref "U1") (pin "17") (pinfunction "SHD/SD2_17") (pintype "bidirectional"))
    )
    (net (code "66") (name "unconnected-(U1-SWP{slash}SD3-Pad18)") (class "Default")
      (node (ref "U1") (pin "18") (pinfunction "SWP/SD3_18") (pintype "bidirectional"))
    )
  )
)
